# sensor-t.net
KiCad netlist of a schematic drawn in EAGLE
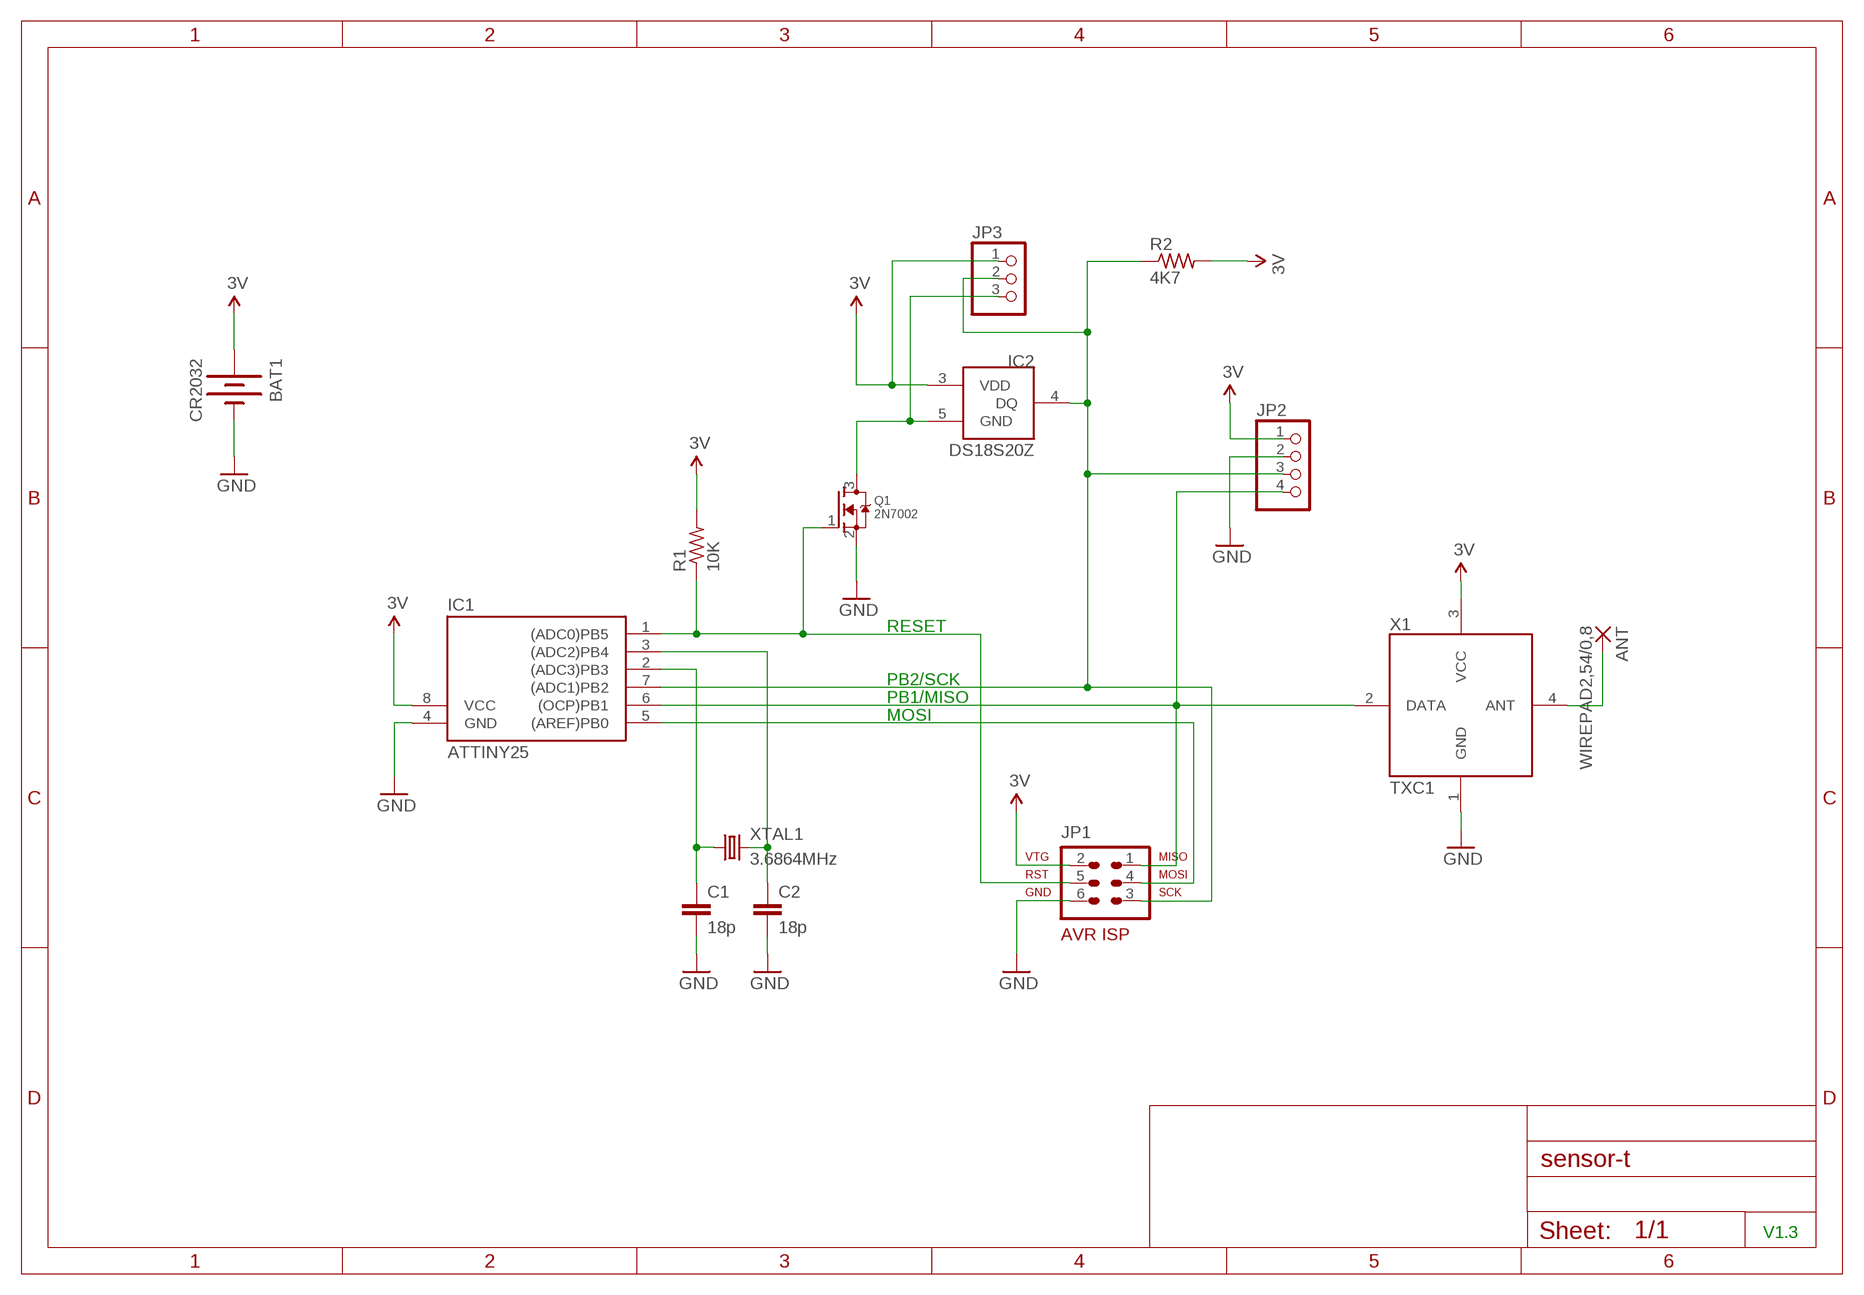
[diagram p0: schematic, sheet 1]

(export (version "E")
  (design (tool "Eeschema 10.0.6"))
  (components
    (comp (ref "ANT")
      (value "WIREPAD2,54/0,8")
      (footprint "eagle-import:2,54_0,8")
      (libsource (lib "eagle-import") (part "WIREPAD2,54/0,8"))
    )
    (comp (ref "BAT1")
      (value "CR2032")
      (footprint "eagle-import:BATTCON_CELL_20MM")
      (libsource (lib "eagle-import") (part "BATTERY"))
    )
    (comp (ref "C1")
      (value "18p")
      (footprint "eagle-import:0805")
      (libsource (lib "eagle-import") (part "CAP0805"))
    )
    (comp (ref "C2")
      (value "18p")
      (footprint "eagle-import:0805")
      (libsource (lib "eagle-import") (part "CAP0805"))
    )
    (comp (ref "IC1")
      (value "ATTINY25")
      (footprint "eagle-import:SOIC8")
      (libsource (lib "eagle-import") (part "TINY25-20SU"))
    )
    (comp (ref "IC2")
      (value "DS18S20Z")
      (footprint "eagle-import:SO08-208")
      (libsource (lib "eagle-import") (part "DS18S20Z"))
    )
    (comp (ref "JP1")
      (value "AVR-ISP-6X1")
      (footprint "eagle-import:1X06")
      (libsource (lib "eagle-import") (part "AVR-ISP-6X1"))
    )
    (comp (ref "JP2")
      (value "PINHD-1X4")
      (footprint "eagle-import:1X04")
      (libsource (lib "eagle-import") (part "PINHD-1X4"))
    )
    (comp (ref "JP3")
      (value "PINHD-1X3")
      (footprint "eagle-import:1X03")
      (libsource (lib "eagle-import") (part "PINHD-1X3"))
    )
    (comp (ref "Q1")
      (value "2N7002")
      (footprint "eagle-import:SOT23")
      (libsource (lib "eagle-import") (part "MOSFET-NREFLOW"))
    )
    (comp (ref "R1")
      (value "10K")
      (footprint "eagle-import:M0805")
      (libsource (lib "eagle-import") (part "R-US_M0805"))
    )
    (comp (ref "R2")
      (value "4K7")
      (footprint "eagle-import:M0805")
      (libsource (lib "eagle-import") (part "R-US_M0805"))
    )
    (comp (ref "X1")
      (value "TXC1")
      (footprint "eagle-import:TXC1")
      (libsource (lib "eagle-import") (part "TXC1"))
    )
    (comp (ref "XTAL1")
      (value "3.6864MHz")
      (footprint "eagle-import:HC49UP")
      (libsource (lib "eagle-import") (part "CRYSTALSMD"))
    )
  )
  (nets
    (net (code "1") (name "3V") (class "Default")
      (node (ref "BAT1") (pin "+VE") (pinfunction "+_+VE") (pintype "power_in"))
      (node (ref "IC1") (pin "8") (pinfunction "VCC_8") (pintype "power_in"))
      (node (ref "IC2") (pin "3") (pinfunction "VDD_3") (pintype "power_in"))
      (node (ref "JP1") (pin "2") (pinfunction "2_2") (pintype "passive"))
      (node (ref "JP2") (pin "1") (pinfunction "1_1") (pintype "passive"))
      (node (ref "JP3") (pin "1") (pinfunction "1_1") (pintype "passive"))
      (node (ref "R1") (pin "2") (pinfunction "2_2") (pintype "passive"))
      (node (ref "R2") (pin "2") (pinfunction "2_2") (pintype "passive"))
      (node (ref "X1") (pin "3") (pinfunction "VCC_3") (pintype "power_in"))
    )
    (net (code "2") (name "GND") (class "Default")
      (node (ref "BAT1") (pin "-VE") (pinfunction "-_-VE") (pintype "power_in"))
      (node (ref "C1") (pin "2") (pinfunction "2_2") (pintype "passive"))
      (node (ref "C2") (pin "2") (pinfunction "2_2") (pintype "passive"))
      (node (ref "IC1") (pin "4") (pinfunction "GND_4") (pintype "power_in"))
      (node (ref "JP1") (pin "6") (pinfunction "6_6") (pintype "passive"))
      (node (ref "JP2") (pin "2") (pinfunction "2_2") (pintype "passive"))
      (node (ref "Q1") (pin "2") (pinfunction "S_2") (pintype "bidirectional"))
      (node (ref "X1") (pin "1") (pinfunction "GND_1") (pintype "power_in"))
    )
    (net (code "3") (name "Net-(ANT-P)") (class "Default")
      (node (ref "ANT") (pin "1") (pinfunction "P_1") (pintype "passive"))
      (node (ref "X1") (pin "4") (pinfunction "ANT_4") (pintype "output"))
    )
    (net (code "4") (name "Net-(IC1-(ADC0)PB5)") (class "Default")
      (node (ref "IC1") (pin "1") (pinfunction "(ADC0)PB5_1") (pintype "bidirectional"))
      (node (ref "JP1") (pin "5") (pinfunction "5_5") (pintype "passive"))
      (node (ref "Q1") (pin "1") (pinfunction "G_1") (pintype "bidirectional"))
      (node (ref "R1") (pin "1") (pinfunction "1_1") (pintype "passive"))
    )
    (net (code "5") (name "Net-(IC1-(ADC1)PB2)") (class "Default")
      (node (ref "IC1") (pin "7") (pinfunction "(ADC1)PB2_7") (pintype "bidirectional"))
      (node (ref "IC2") (pin "4") (pinfunction "DQ_4") (pintype "bidirectional"))
      (node (ref "JP1") (pin "3") (pinfunction "3_3") (pintype "passive"))
      (node (ref "JP2") (pin "3") (pinfunction "3_3") (pintype "passive"))
      (node (ref "JP3") (pin "2") (pinfunction "2_2") (pintype "passive"))
      (node (ref "R2") (pin "1") (pinfunction "1_1") (pintype "passive"))
    )
    (net (code "6") (name "Net-(IC1-(ADC2)PB4)") (class "Default")
      (node (ref "C2") (pin "1") (pinfunction "1_1") (pintype "passive"))
      (node (ref "IC1") (pin "3") (pinfunction "(ADC2)PB4_3") (pintype "bidirectional"))
      (node (ref "XTAL1") (pin "2") (pinfunction "2_2") (pintype "passive"))
    )
    (net (code "7") (name "Net-(IC1-(ADC3)PB3)") (class "Default")
      (node (ref "C1") (pin "1") (pinfunction "1_1") (pintype "passive"))
      (node (ref "IC1") (pin "2") (pinfunction "(ADC3)PB3_2") (pintype "bidirectional"))
      (node (ref "XTAL1") (pin "1") (pinfunction "1_1") (pintype "passive"))
    )
    (net (code "8") (name "Net-(IC1-(AREF)PB0)") (class "Default")
      (node (ref "IC1") (pin "5") (pinfunction "(AREF)PB0_5") (pintype "bidirectional"))
      (node (ref "JP1") (pin "4") (pinfunction "4_4") (pintype "passive"))
    )
    (net (code "9") (name "Net-(IC1-(OCP)PB1)") (class "Default")
      (node (ref "IC1") (pin "6") (pinfunction "(OCP)PB1_6") (pintype "bidirectional"))
      (node (ref "JP1") (pin "1") (pinfunction "1_1") (pintype "passive"))
      (node (ref "JP2") (pin "4") (pinfunction "4_4") (pintype "passive"))
      (node (ref "X1") (pin "2") (pinfunction "DATA_2") (pintype "input"))
    )
    (net (code "10") (name "Net-(IC2-GND)") (class "Default")
      (node (ref "IC2") (pin "5") (pinfunction "GND_5") (pintype "power_in"))
      (node (ref "JP3") (pin "3") (pinfunction "3_3") (pintype "passive"))
      (node (ref "Q1") (pin "3") (pinfunction "D_3") (pintype "bidirectional"))
    )
  )
)
